# untitled.net
KiCad netlist of a schematic drawn in EAGLE
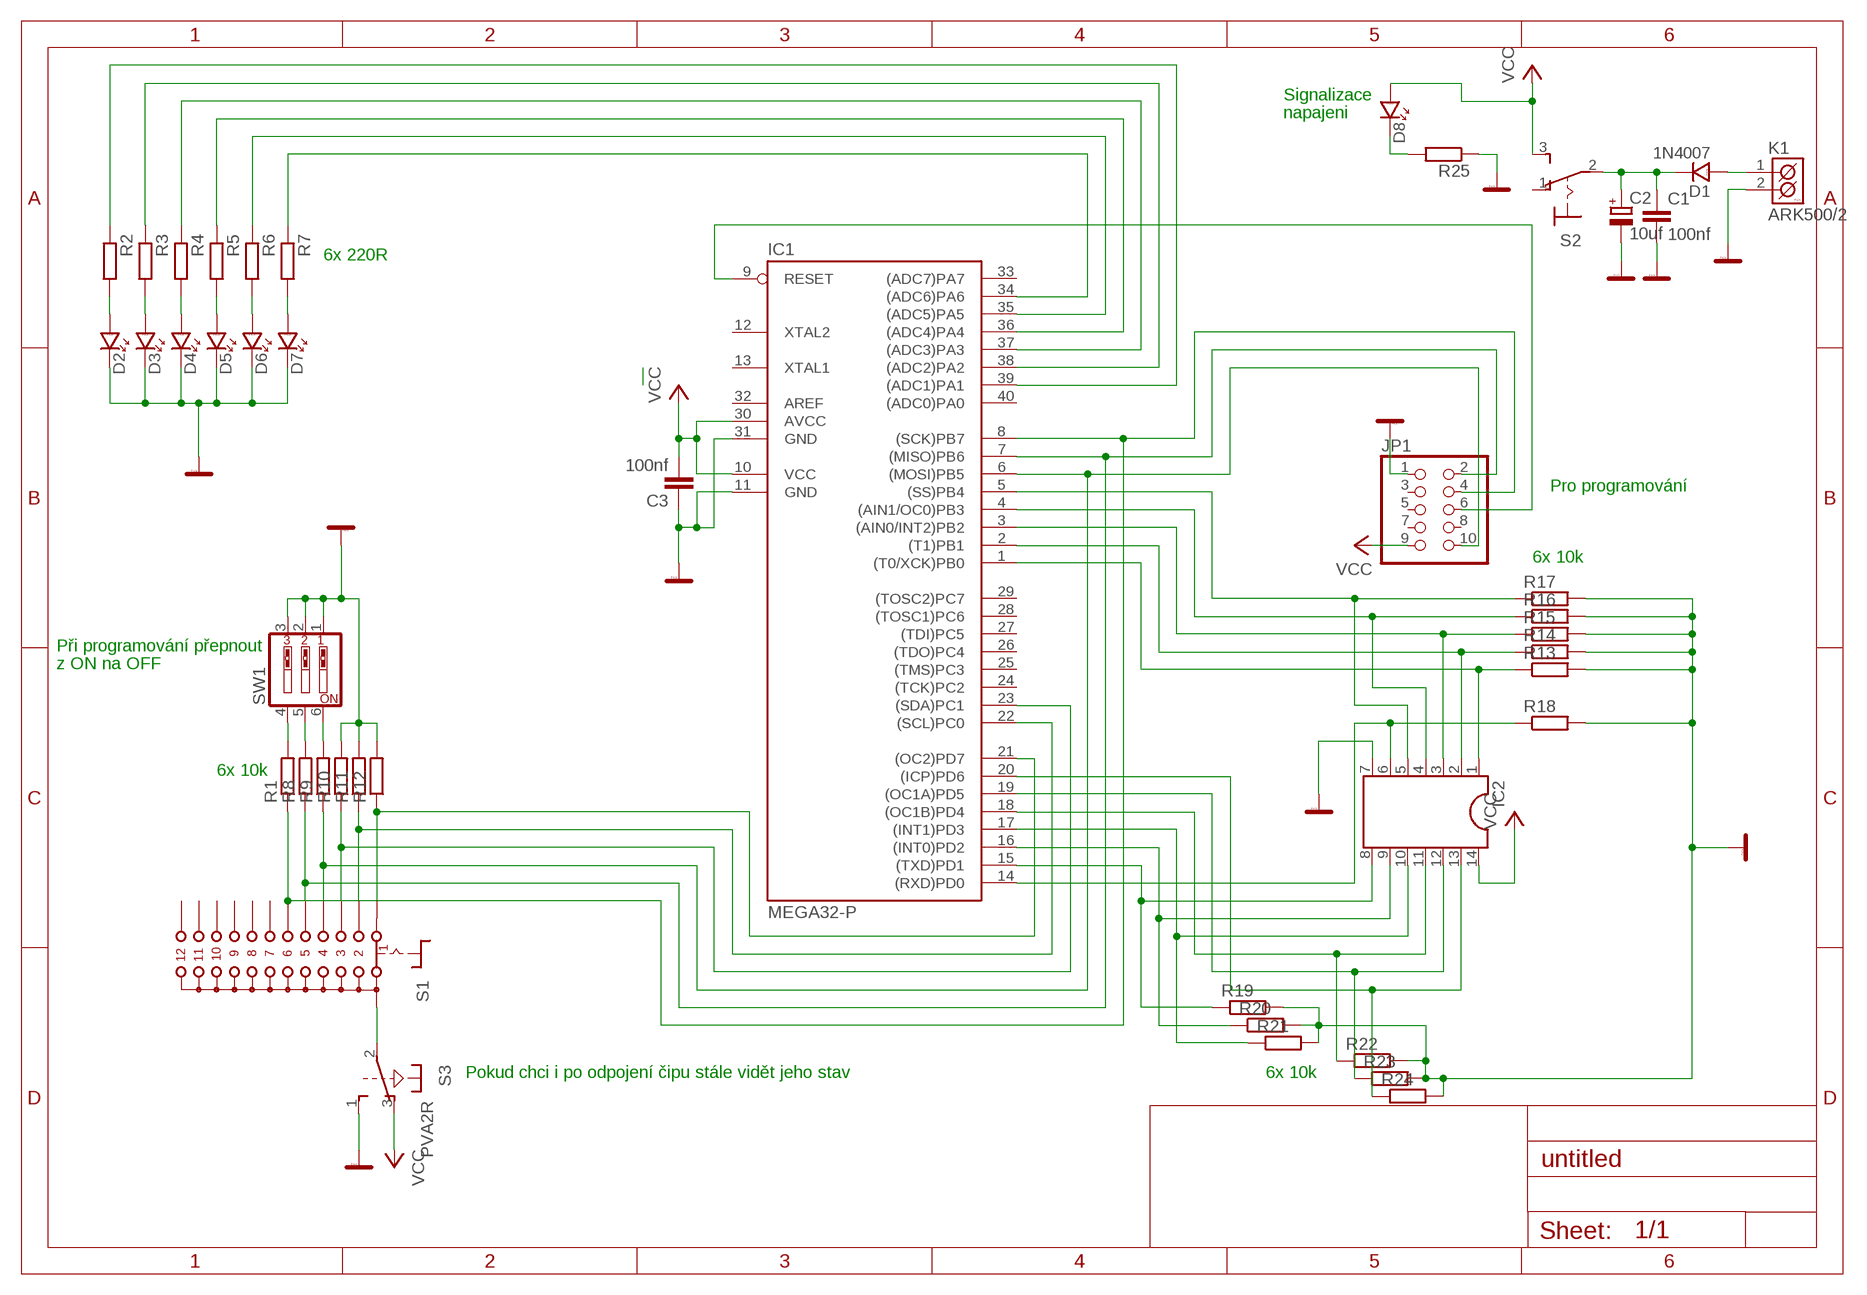
[diagram p0: schematic, sheet 1]

(export (version "E")
  (design (tool "Eeschema 10.0.6"))
  (components
    (comp (ref "C1")
      (value "100nf")
      (footprint "eagle-import:C050-025X075")
      (libsource (lib "eagle-import") (part "C-EU050-025X075"))
    )
    (comp (ref "C2")
      (value "10uf")
      (footprint "eagle-import:E5-8,5")
      (libsource (lib "eagle-import") (part "CPOL-EUE5-8.5"))
    )
    (comp (ref "C3")
      (value "100nf")
      (footprint "eagle-import:C050-025X075")
      (libsource (lib "eagle-import") (part "C-EU050-025X075"))
    )
    (comp (ref "D1")
      (value "1N4007")
      (footprint "eagle-import:DO41")
      (libsource (lib "eagle-import") (part "1N4007"))
    )
    (comp (ref "D2")
      (value "LED_5")
      (footprint "eagle-import:LED_5")
      (libsource (lib "eagle-import") (part "LED_5"))
    )
    (comp (ref "D3")
      (value "LED_5")
      (footprint "eagle-import:LED_5")
      (libsource (lib "eagle-import") (part "LED_5"))
    )
    (comp (ref "D4")
      (value "LED_5")
      (footprint "eagle-import:LED_5")
      (libsource (lib "eagle-import") (part "LED_5"))
    )
    (comp (ref "D5")
      (value "LED_5")
      (footprint "eagle-import:LED_5")
      (libsource (lib "eagle-import") (part "LED_5"))
    )
    (comp (ref "D6")
      (value "LED_5")
      (footprint "eagle-import:LED_5")
      (libsource (lib "eagle-import") (part "LED_5"))
    )
    (comp (ref "D7")
      (value "LED_5")
      (footprint "eagle-import:LED_5")
      (libsource (lib "eagle-import") (part "LED_5"))
    )
    (comp (ref "D8")
      (value "LED_5")
      (footprint "eagle-import:LED_5")
      (libsource (lib "eagle-import") (part "LED_5"))
    )
    (comp (ref "IC1")
      (value "MEGA32-P")
      (footprint "eagle-import:DIL40")
      (fields (field (name "MPN") "ATMEGA32-16PU"))
      (libsource (lib "eagle-import") (part "MEGA32-P"))
    )
    (comp (ref "IC2")
      (value "DIL14")
      (footprint "eagle-import:DIL14")
      (libsource (lib "eagle-import") (part "DIL14"))
    )
    (comp (ref "JP1")
      (value "PINHD-2X5")
      (footprint "eagle-import:2X05")
      (libsource (lib "eagle-import") (part "PINHD-2X5"))
    )
    (comp (ref "K1")
      (value "ARK500/2")
      (footprint "eagle-import:ARK500_2")
      (libsource (lib "eagle-import") (part "ARK500/2"))
    )
    (comp (ref "R1")
      (value "R-EU_0207/10")
      (footprint "eagle-import:0207_10")
      (libsource (lib "eagle-import") (part "resistor_R-EU_0207/10"))
    )
    (comp (ref "R2")
      (value "R-EU_0207/10")
      (footprint "eagle-import:0207_10")
      (libsource (lib "eagle-import") (part "R-EU_0207/10"))
    )
    (comp (ref "R3")
      (value "R-EU_0207/10")
      (footprint "eagle-import:0207_10")
      (libsource (lib "eagle-import") (part "R-EU_0207/10"))
    )
    (comp (ref "R4")
      (value "R-EU_0207/10")
      (footprint "eagle-import:0207_10")
      (libsource (lib "eagle-import") (part "R-EU_0207/10"))
    )
    (comp (ref "R5")
      (value "R-EU_0207/10")
      (footprint "eagle-import:0207_10")
      (libsource (lib "eagle-import") (part "R-EU_0207/10"))
    )
    (comp (ref "R6")
      (value "R-EU_0207/10")
      (footprint "eagle-import:0207_10")
      (libsource (lib "eagle-import") (part "R-EU_0207/10"))
    )
    (comp (ref "R7")
      (value "R-EU_0207/10")
      (footprint "eagle-import:0207_10")
      (libsource (lib "eagle-import") (part "R-EU_0207/10"))
    )
    (comp (ref "R8")
      (value "R-EU_0207/10")
      (footprint "eagle-import:0207_10")
      (libsource (lib "eagle-import") (part "resistor_R-EU_0207/10"))
    )
    (comp (ref "R9")
      (value "R-EU_0207/10")
      (footprint "eagle-import:0207_10")
      (libsource (lib "eagle-import") (part "resistor_R-EU_0207/10"))
    )
    (comp (ref "R10")
      (value "R-EU_0207/10")
      (footprint "eagle-import:0207_10")
      (libsource (lib "eagle-import") (part "resistor_R-EU_0207/10"))
    )
    (comp (ref "R11")
      (value "R-EU_0207/10")
      (footprint "eagle-import:0207_10")
      (libsource (lib "eagle-import") (part "resistor_R-EU_0207/10"))
    )
    (comp (ref "R12")
      (value "R-EU_0207/10")
      (footprint "eagle-import:0207_10")
      (libsource (lib "eagle-import") (part "resistor_R-EU_0207/10"))
    )
    (comp (ref "R13")
      (value "R-EU_0207/10")
      (footprint "eagle-import:0207_10")
      (libsource (lib "eagle-import") (part "resistor_R-EU_0207/10"))
    )
    (comp (ref "R14")
      (value "R-EU_0207/10")
      (footprint "eagle-import:0207_10")
      (libsource (lib "eagle-import") (part "resistor_R-EU_0207/10"))
    )
    (comp (ref "R15")
      (value "R-EU_0207/10")
      (footprint "eagle-import:0207_10")
      (libsource (lib "eagle-import") (part "resistor_R-EU_0207/10"))
    )
    (comp (ref "R16")
      (value "R-EU_0207/10")
      (footprint "eagle-import:0207_10")
      (libsource (lib "eagle-import") (part "resistor_R-EU_0207/10"))
    )
    (comp (ref "R17")
      (value "R-EU_0207/10")
      (footprint "eagle-import:0207_10")
      (libsource (lib "eagle-import") (part "resistor_R-EU_0207/10"))
    )
    (comp (ref "R18")
      (value "R-EU_0207/10")
      (footprint "eagle-import:0207_10")
      (libsource (lib "eagle-import") (part "resistor_R-EU_0207/10"))
    )
    (comp (ref "R19")
      (value "R-EU_0207/10")
      (footprint "eagle-import:0207_10")
      (libsource (lib "eagle-import") (part "resistor_R-EU_0207/10"))
    )
    (comp (ref "R20")
      (value "R-EU_0207/10")
      (footprint "eagle-import:0207_10")
      (libsource (lib "eagle-import") (part "resistor_R-EU_0207/10"))
    )
    (comp (ref "R21")
      (value "R-EU_0207/10")
      (footprint "eagle-import:0207_10")
      (libsource (lib "eagle-import") (part "resistor_R-EU_0207/10"))
    )
    (comp (ref "R22")
      (value "R-EU_0207/10")
      (footprint "eagle-import:0207_10")
      (libsource (lib "eagle-import") (part "resistor_R-EU_0207/10"))
    )
    (comp (ref "R23")
      (value "R-EU_0207/10")
      (footprint "eagle-import:0207_10")
      (libsource (lib "eagle-import") (part "resistor_R-EU_0207/10"))
    )
    (comp (ref "R24")
      (value "R-EU_0207/10")
      (footprint "eagle-import:0207_10")
      (libsource (lib "eagle-import") (part "resistor_R-EU_0207/10"))
    )
    (comp (ref "R25")
      (value "R-EU_0207/10")
      (footprint "eagle-import:0207_10")
      (libsource (lib "eagle-import") (part "resistor_R-EU_0207/10"))
    )
    (comp (ref "S1")
      (value "CK101X12")
      (footprint "eagle-import:CK101X12")
      (libsource (lib "eagle-import") (part "CK101X12"))
    )
    (comp (ref "S2")
      (value "320-916")
      (footprint "eagle-import:320-916")
      (libsource (lib "eagle-import") (part "320-916"))
    )
    (comp (ref "S3")
      (value "PVA2R")
      (footprint "eagle-import:PVA2R")
      (libsource (lib "eagle-import") (part "PVA2R"))
    )
    (comp (ref "SW1")
      (value "SW_DIP-3")
      (footprint "eagle-import:EDG-03")
      (libsource (lib "eagle-import") (part "SW_DIP-3"))
    )
  )
  (nets
    (net (code "1") (name "GND") (class "Default")
      (node (ref "C1") (pin "2") (pinfunction "2_2") (pintype "passive"))
      (node (ref "C2") (pin "-") (pinfunction "-_-") (pintype "passive"))
      (node (ref "C3") (pin "1") (pinfunction "1_1") (pintype "passive"))
      (node (ref "D2") (pin "K") (pinfunction "K_K") (pintype "passive"))
      (node (ref "D3") (pin "K") (pinfunction "K_K") (pintype "passive"))
      (node (ref "D4") (pin "K") (pinfunction "K_K") (pintype "passive"))
      (node (ref "D5") (pin "K") (pinfunction "K_K") (pintype "passive"))
      (node (ref "D6") (pin "K") (pinfunction "K_K") (pintype "passive"))
      (node (ref "D7") (pin "K") (pinfunction "K_K") (pintype "passive"))
      (node (ref "IC1") (pin "11") (pinfunction "GND_11") (pintype "power_in"))
      (node (ref "IC1") (pin "31") (pinfunction "GND_31") (pintype "power_in"))
      (node (ref "IC2") (pin "7") (pinfunction "7_7") (pintype "passive"))
      (node (ref "JP1") (pin "1") (pinfunction "1_1") (pintype "passive"))
      (node (ref "K1") (pin "2") (pinfunction "K2_2") (pintype "passive"))
      (node (ref "R10") (pin "2") (pinfunction "2_2") (pintype "passive"))
      (node (ref "R11") (pin "2") (pinfunction "2_2") (pintype "passive"))
      (node (ref "R12") (pin "2") (pinfunction "2_2") (pintype "passive"))
      (node (ref "R13") (pin "2") (pinfunction "2_2") (pintype "passive"))
      (node (ref "R14") (pin "2") (pinfunction "2_2") (pintype "passive"))
      (node (ref "R15") (pin "2") (pinfunction "2_2") (pintype "passive"))
      (node (ref "R16") (pin "2") (pinfunction "2_2") (pintype "passive"))
      (node (ref "R17") (pin "2") (pinfunction "2_2") (pintype "passive"))
      (node (ref "R18") (pin "2") (pinfunction "2_2") (pintype "passive"))
      (node (ref "R19") (pin "2") (pinfunction "2_2") (pintype "passive"))
      (node (ref "R20") (pin "2") (pinfunction "2_2") (pintype "passive"))
      (node (ref "R21") (pin "2") (pinfunction "2_2") (pintype "passive"))
      (node (ref "R22") (pin "2") (pinfunction "2_2") (pintype "passive"))
      (node (ref "R23") (pin "2") (pinfunction "2_2") (pintype "passive"))
      (node (ref "R24") (pin "2") (pinfunction "2_2") (pintype "passive"))
      (node (ref "R25") (pin "1") (pinfunction "1_1") (pintype "passive"))
      (node (ref "S3") (pin "1") (pinfunction "S_1") (pintype "passive"))
      (node (ref "SW1") (pin "1") (pinfunction "1_1") (pintype "passive"))
      (node (ref "SW1") (pin "2") (pinfunction "2_2") (pintype "passive"))
      (node (ref "SW1") (pin "3") (pinfunction "3_3") (pintype "passive"))
    )
    (net (code "2") (name "Net-(D2-PadA)") (class "Default")
      (node (ref "D2") (pin "A") (pinfunction "A_A") (pintype "passive"))
      (node (ref "R2") (pin "2") (pinfunction "2_2") (pintype "passive"))
    )
    (net (code "3") (name "Net-(D3-PadA)") (class "Default")
      (node (ref "D3") (pin "A") (pinfunction "A_A") (pintype "passive"))
      (node (ref "R3") (pin "2") (pinfunction "2_2") (pintype "passive"))
    )
    (net (code "4") (name "Net-(D4-PadA)") (class "Default")
      (node (ref "D4") (pin "A") (pinfunction "A_A") (pintype "passive"))
      (node (ref "R4") (pin "2") (pinfunction "2_2") (pintype "passive"))
    )
    (net (code "5") (name "Net-(D5-PadA)") (class "Default")
      (node (ref "D5") (pin "A") (pinfunction "A_A") (pintype "passive"))
      (node (ref "R5") (pin "2") (pinfunction "2_2") (pintype "passive"))
    )
    (net (code "6") (name "Net-(D6-PadA)") (class "Default")
      (node (ref "D6") (pin "A") (pinfunction "A_A") (pintype "passive"))
      (node (ref "R6") (pin "2") (pinfunction "2_2") (pintype "passive"))
    )
    (net (code "7") (name "Net-(D7-PadA)") (class "Default")
      (node (ref "D7") (pin "A") (pinfunction "A_A") (pintype "passive"))
      (node (ref "R7") (pin "2") (pinfunction "2_2") (pintype "passive"))
    )
    (net (code "8") (name "Net-(D8-PadK)") (class "Default")
      (node (ref "D8") (pin "K") (pinfunction "K_K") (pintype "passive"))
      (node (ref "R25") (pin "2") (pinfunction "2_2") (pintype "passive"))
    )
    (net (code "9") (name "Net-(IC1-(ADC1)PA1)") (class "Default")
      (node (ref "IC1") (pin "39") (pinfunction "(ADC1)PA1_39") (pintype "bidirectional"))
      (node (ref "R2") (pin "1") (pinfunction "1_1") (pintype "passive"))
    )
    (net (code "10") (name "Net-(IC1-(ADC2)PA2)") (class "Default")
      (node (ref "IC1") (pin "38") (pinfunction "(ADC2)PA2_38") (pintype "bidirectional"))
      (node (ref "R3") (pin "1") (pinfunction "1_1") (pintype "passive"))
    )
    (net (code "11") (name "Net-(IC1-(ADC3)PA3)") (class "Default")
      (node (ref "IC1") (pin "37") (pinfunction "(ADC3)PA3_37") (pintype "bidirectional"))
      (node (ref "R4") (pin "1") (pinfunction "1_1") (pintype "passive"))
    )
    (net (code "12") (name "Net-(IC1-(ADC4)PA4)") (class "Default")
      (node (ref "IC1") (pin "36") (pinfunction "(ADC4)PA4_36") (pintype "bidirectional"))
      (node (ref "R5") (pin "1") (pinfunction "1_1") (pintype "passive"))
    )
    (net (code "13") (name "Net-(IC1-(ADC5)PA5)") (class "Default")
      (node (ref "IC1") (pin "35") (pinfunction "(ADC5)PA5_35") (pintype "bidirectional"))
      (node (ref "R6") (pin "1") (pinfunction "1_1") (pintype "passive"))
    )
    (net (code "14") (name "Net-(IC1-(ADC6)PA6)") (class "Default")
      (node (ref "IC1") (pin "34") (pinfunction "(ADC6)PA6_34") (pintype "bidirectional"))
      (node (ref "R7") (pin "1") (pinfunction "1_1") (pintype "passive"))
    )
    (net (code "15") (name "Net-(IC1-(AIN0{slash}INT2)PB2)") (class "Default")
      (node (ref "IC1") (pin "3") (pinfunction "(AIN0/INT2)PB2_3") (pintype "bidirectional"))
      (node (ref "IC2") (pin "3") (pinfunction "3_3") (pintype "passive"))
      (node (ref "R15") (pin "1") (pinfunction "1_1") (pintype "passive"))
    )
    (net (code "16") (name "Net-(IC1-(AIN1{slash}OC0)PB3)") (class "Default")
      (node (ref "IC1") (pin "4") (pinfunction "(AIN1/OC0)PB3_4") (pintype "bidirectional"))
      (node (ref "IC2") (pin "4") (pinfunction "4_4") (pintype "passive"))
      (node (ref "R16") (pin "1") (pinfunction "1_1") (pintype "passive"))
    )
    (net (code "17") (name "Net-(IC1-(ICP)PD6)") (class "Default")
      (node (ref "IC1") (pin "20") (pinfunction "(ICP)PD6_20") (pintype "bidirectional"))
      (node (ref "IC2") (pin "13") (pinfunction "13_13") (pintype "passive"))
      (node (ref "R24") (pin "1") (pinfunction "1_1") (pintype "passive"))
    )
    (net (code "18") (name "Net-(IC1-(INT0)PD2)") (class "Default")
      (node (ref "IC1") (pin "16") (pinfunction "(INT0)PD2_16") (pintype "bidirectional"))
      (node (ref "IC2") (pin "9") (pinfunction "9_9") (pintype "passive"))
      (node (ref "R20") (pin "1") (pinfunction "1_1") (pintype "passive"))
    )
    (net (code "19") (name "Net-(IC1-(INT1)PD3)") (class "Default")
      (node (ref "IC1") (pin "17") (pinfunction "(INT1)PD3_17") (pintype "bidirectional"))
      (node (ref "IC2") (pin "10") (pinfunction "10_10") (pintype "passive"))
      (node (ref "R21") (pin "1") (pinfunction "1_1") (pintype "passive"))
    )
    (net (code "20") (name "Net-(IC1-(MISO)PB6)") (class "Default")
      (node (ref "IC1") (pin "7") (pinfunction "(MISO)PB6_7") (pintype "bidirectional"))
      (node (ref "JP1") (pin "2") (pinfunction "2_2") (pintype "passive"))
      (node (ref "R8") (pin "1") (pinfunction "1_1") (pintype "passive"))
      (node (ref "S1") (pin "5") (pinfunction "5_5") (pintype "passive"))
    )
    (net (code "21") (name "Net-(IC1-(MOSI)PB5)") (class "Default")
      (node (ref "IC1") (pin "6") (pinfunction "(MOSI)PB5_6") (pintype "bidirectional"))
      (node (ref "JP1") (pin "10") (pinfunction "10_10") (pintype "passive"))
      (node (ref "R9") (pin "1") (pinfunction "1_1") (pintype "passive"))
      (node (ref "S1") (pin "4") (pinfunction "4_4") (pintype "passive"))
    )
    (net (code "22") (name "Net-(IC1-(OC1A)PD5)") (class "Default")
      (node (ref "IC1") (pin "19") (pinfunction "(OC1A)PD5_19") (pintype "bidirectional"))
      (node (ref "IC2") (pin "12") (pinfunction "12_12") (pintype "passive"))
      (node (ref "R23") (pin "1") (pinfunction "1_1") (pintype "passive"))
    )
    (net (code "23") (name "Net-(IC1-(OC1B)PD4)") (class "Default")
      (node (ref "IC1") (pin "18") (pinfunction "(OC1B)PD4_18") (pintype "bidirectional"))
      (node (ref "IC2") (pin "11") (pinfunction "11_11") (pintype "passive"))
      (node (ref "R22") (pin "1") (pinfunction "1_1") (pintype "passive"))
    )
    (net (code "24") (name "Net-(IC1-(OC2)PD7)") (class "Default")
      (node (ref "IC1") (pin "21") (pinfunction "(OC2)PD7_21") (pintype "bidirectional"))
      (node (ref "R12") (pin "1") (pinfunction "1_1") (pintype "passive"))
      (node (ref "S1") (pin "1") (pinfunction "1_1") (pintype "passive"))
    )
    (net (code "25") (name "Net-(IC1-(RXD)PD0)") (class "Default")
      (node (ref "IC1") (pin "14") (pinfunction "(RXD)PD0_14") (pintype "bidirectional"))
      (node (ref "IC2") (pin "6") (pinfunction "6_6") (pintype "passive"))
      (node (ref "R18") (pin "1") (pinfunction "1_1") (pintype "passive"))
    )
    (net (code "26") (name "Net-(IC1-(SCK)PB7)") (class "Default")
      (node (ref "IC1") (pin "8") (pinfunction "(SCK)PB7_8") (pintype "bidirectional"))
      (node (ref "JP1") (pin "4") (pinfunction "4_4") (pintype "passive"))
      (node (ref "R1") (pin "1") (pinfunction "1_1") (pintype "passive"))
      (node (ref "S1") (pin "6") (pinfunction "6_6") (pintype "passive"))
    )
    (net (code "27") (name "Net-(IC1-(SCL)PC0)") (class "Default")
      (node (ref "IC1") (pin "22") (pinfunction "(SCL)PC0_22") (pintype "bidirectional"))
      (node (ref "R11") (pin "1") (pinfunction "1_1") (pintype "passive"))
      (node (ref "S1") (pin "2") (pinfunction "2_2") (pintype "passive"))
    )
    (net (code "28") (name "Net-(IC1-(SDA)PC1)") (class "Default")
      (node (ref "IC1") (pin "23") (pinfunction "(SDA)PC1_23") (pintype "bidirectional"))
      (node (ref "R10") (pin "1") (pinfunction "1_1") (pintype "passive"))
      (node (ref "S1") (pin "3") (pinfunction "3_3") (pintype "passive"))
    )
    (net (code "29") (name "Net-(IC1-(SS)PB4)") (class "Default")
      (node (ref "IC1") (pin "5") (pinfunction "(SS)PB4_5") (pintype "bidirectional"))
      (node (ref "IC2") (pin "5") (pinfunction "5_5") (pintype "passive"))
      (node (ref "R17") (pin "1") (pinfunction "1_1") (pintype "passive"))
    )
    (net (code "30") (name "Net-(IC1-(T0{slash}XCK)PB0)") (class "Default")
      (node (ref "IC1") (pin "1") (pinfunction "(T0/XCK)PB0_1") (pintype "bidirectional"))
      (node (ref "IC2") (pin "1") (pinfunction "1_1") (pintype "passive"))
      (node (ref "R13") (pin "1") (pinfunction "1_1") (pintype "passive"))
    )
    (net (code "31") (name "Net-(IC1-(T1)PB1)") (class "Default")
      (node (ref "IC1") (pin "2") (pinfunction "(T1)PB1_2") (pintype "bidirectional"))
      (node (ref "IC2") (pin "2") (pinfunction "2_2") (pintype "passive"))
      (node (ref "R14") (pin "1") (pinfunction "1_1") (pintype "passive"))
    )
    (net (code "32") (name "Net-(IC1-(TXD)PD1)") (class "Default")
      (node (ref "IC1") (pin "15") (pinfunction "(TXD)PD1_15") (pintype "bidirectional"))
      (node (ref "IC2") (pin "8") (pinfunction "8_8") (pintype "passive"))
      (node (ref "R19") (pin "1") (pinfunction "1_1") (pintype "passive"))
    )
    (net (code "33") (name "Net-(IC1-RESET)") (class "Default")
      (node (ref "IC1") (pin "9") (pinfunction "RESET_9") (pintype "input"))
      (node (ref "JP1") (pin "6") (pinfunction "6_6") (pintype "passive"))
    )
    (net (code "34") (name "Net-(K1-K1)") (class "Default")
      (node (ref "D1") (pin "A") (pinfunction "A_A") (pintype "passive"))
      (node (ref "K1") (pin "1") (pinfunction "K1_1") (pintype "passive"))
    )
    (net (code "35") (name "Net-(R1-Pad2)") (class "Default")
      (node (ref "R1") (pin "2") (pinfunction "2_2") (pintype "passive"))
      (node (ref "SW1") (pin "4") (pinfunction "4_4") (pintype "passive"))
    )
    (net (code "36") (name "Net-(R8-Pad2)") (class "Default")
      (node (ref "R8") (pin "2") (pinfunction "2_2") (pintype "passive"))
      (node (ref "SW1") (pin "5") (pinfunction "5_5") (pintype "passive"))
    )
    (net (code "37") (name "Net-(R9-Pad2)") (class "Default")
      (node (ref "R9") (pin "2") (pinfunction "2_2") (pintype "passive"))
      (node (ref "SW1") (pin "6") (pinfunction "6_6") (pintype "passive"))
    )
    (net (code "38") (name "Net-(S2-P)") (class "Default")
      (node (ref "C1") (pin "1") (pinfunction "1_1") (pintype "passive"))
      (node (ref "C2") (pin "+") (pinfunction "+_+") (pintype "passive"))
      (node (ref "D1") (pin "K") (pinfunction "K_K") (pintype "passive"))
      (node (ref "S2") (pin "2") (pinfunction "P_2") (pintype "passive"))
    )
    (net (code "39") (name "Net-(S3A-P)") (class "Default")
      (node (ref "S1") (pin "A") (pinfunction "A_A") (pintype "passive"))
      (node (ref "S3") (pin "2") (pinfunction "P_2") (pintype "passive"))
    )
    (net (code "40") (name "VCC") (class "Default")
      (node (ref "C3") (pin "2") (pinfunction "2_2") (pintype "passive"))
      (node (ref "D8") (pin "A") (pinfunction "A_A") (pintype "passive"))
      (node (ref "IC1") (pin "10") (pinfunction "VCC_10") (pintype "power_in"))
      (node (ref "IC1") (pin "30") (pinfunction "AVCC_30") (pintype "power_in"))
      (node (ref "IC2") (pin "14") (pinfunction "14_14") (pintype "passive"))
      (node (ref "JP1") (pin "9") (pinfunction "9_9") (pintype "passive"))
      (node (ref "S2") (pin "3") (pinfunction "S_3") (pintype "passive"))
      (node (ref "S3") (pin "3") (pinfunction "O_3") (pintype "passive"))
    )
    (net (code "41") (name "unconnected-(IC1-(ADC0)PA0-Pad40)") (class "Default")
      (node (ref "IC1") (pin "40") (pinfunction "(ADC0)PA0_40") (pintype "bidirectional"))
    )
    (net (code "42") (name "unconnected-(IC1-(ADC7)PA7-Pad33)") (class "Default")
      (node (ref "IC1") (pin "33") (pinfunction "(ADC7)PA7_33") (pintype "bidirectional"))
    )
    (net (code "43") (name "unconnected-(IC1-(TCK)PC2-Pad24)") (class "Default")
      (node (ref "IC1") (pin "24") (pinfunction "(TCK)PC2_24") (pintype "bidirectional"))
    )
    (net (code "44") (name "unconnected-(IC1-(TDI)PC5-Pad27)") (class "Default")
      (node (ref "IC1") (pin "27") (pinfunction "(TDI)PC5_27") (pintype "bidirectional"))
    )
    (net (code "45") (name "unconnected-(IC1-(TDO)PC4-Pad26)") (class "Default")
      (node (ref "IC1") (pin "26") (pinfunction "(TDO)PC4_26") (pintype "bidirectional"))
    )
    (net (code "46") (name "unconnected-(IC1-(TMS)PC3-Pad25)") (class "Default")
      (node (ref "IC1") (pin "25") (pinfunction "(TMS)PC3_25") (pintype "bidirectional"))
    )
    (net (code "47") (name "unconnected-(IC1-(TOSC1)PC6-Pad28)") (class "Default")
      (node (ref "IC1") (pin "28") (pinfunction "(TOSC1)PC6_28") (pintype "bidirectional"))
    )
    (net (code "48") (name "unconnected-(IC1-(TOSC2)PC7-Pad29)") (class "Default")
      (node (ref "IC1") (pin "29") (pinfunction "(TOSC2)PC7_29") (pintype "bidirectional"))
    )
    (net (code "49") (name "unconnected-(IC1-AREF-Pad32)") (class "Default")
      (node (ref "IC1") (pin "32") (pinfunction "AREF_32") (pintype "passive"))
    )
    (net (code "50") (name "unconnected-(IC1-XTAL1-Pad13)") (class "Default")
      (node (ref "IC1") (pin "13") (pinfunction "XTAL1_13") (pintype "bidirectional"))
    )
    (net (code "51") (name "unconnected-(IC1-XTAL2-Pad12)") (class "Default")
      (node (ref "IC1") (pin "12") (pinfunction "XTAL2_12") (pintype "bidirectional"))
    )
    (net (code "52") (name "unconnected-(JP1-Pad3)") (class "Default")
      (node (ref "JP1") (pin "3") (pinfunction "3_3") (pintype "passive"))
    )
    (net (code "53") (name "unconnected-(JP1-Pad5)") (class "Default")
      (node (ref "JP1") (pin "5") (pinfunction "5_5") (pintype "passive"))
    )
    (net (code "54") (name "unconnected-(JP1-Pad7)") (class "Default")
      (node (ref "JP1") (pin "7") (pinfunction "7_7") (pintype "passive"))
    )
    (net (code "55") (name "unconnected-(JP1-Pad8)") (class "Default")
      (node (ref "JP1") (pin "8") (pinfunction "8_8") (pintype "passive"))
    )
    (net (code "56") (name "unconnected-(S1-Pad7)") (class "Default")
      (node (ref "S1") (pin "7") (pinfunction "7_7") (pintype "passive"))
    )
    (net (code "57") (name "unconnected-(S1-Pad8)") (class "Default")
      (node (ref "S1") (pin "8") (pinfunction "8_8") (pintype "passive"))
    )
    (net (code "58") (name "unconnected-(S1-Pad9)") (class "Default")
      (node (ref "S1") (pin "9") (pinfunction "9_9") (pintype "passive"))
    )
    (net (code "59") (name "unconnected-(S1-Pad10)") (class "Default")
      (node (ref "S1") (pin "10") (pinfunction "10_10") (pintype "passive"))
    )
    (net (code "60") (name "unconnected-(S1-Pad11)") (class "Default")
      (node (ref "S1") (pin "11") (pinfunction "11_11") (pintype "passive"))
    )
    (net (code "61") (name "unconnected-(S1-Pad12)") (class "Default")
      (node (ref "S1") (pin "12") (pinfunction "12_12") (pintype "passive"))
    )
    (net (code "62") (name "unconnected-(S2-O-Pad1)") (class "Default")
      (node (ref "S2") (pin "1") (pinfunction "O_1") (pintype "passive"))
    )
  )
)
